# eBox_relay.net
KiCad netlist of a schematic drawn in Altium Designer
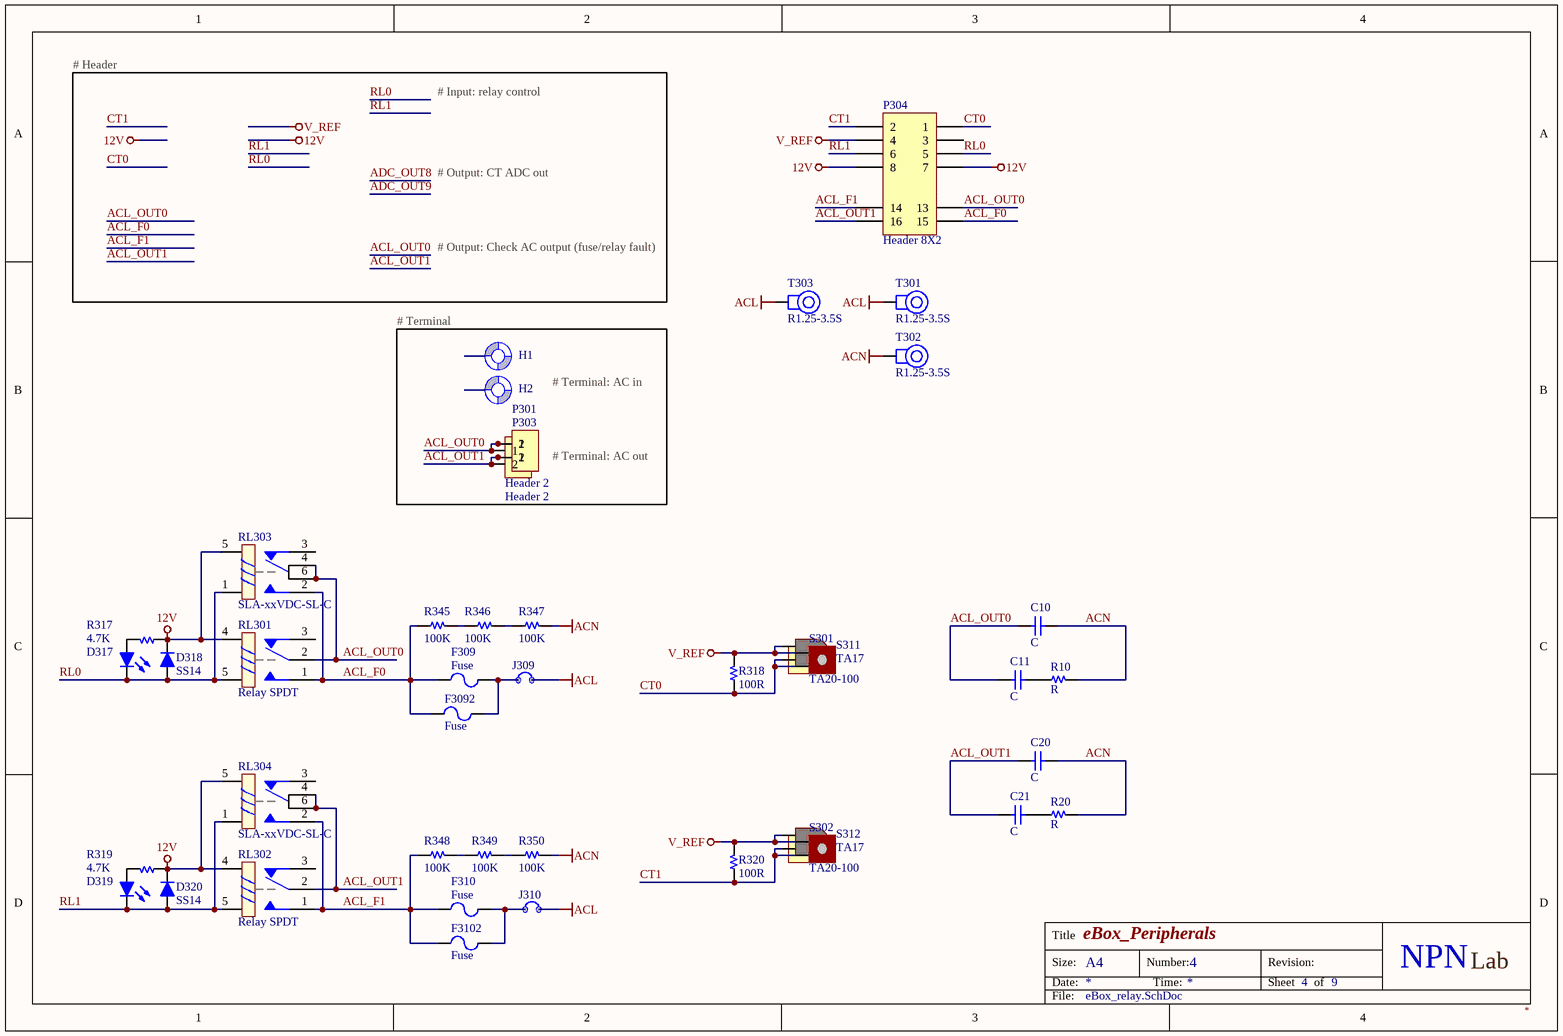
[diagram p0: eBox_relay.SchDoc]

(export (version "E")
  (design (tool "Eeschema 10.0.6"))
  (components
    (comp (ref "C10")
      (value "C")
      (footprint "CAP Ceramic/W300")
      (description "Capacitor non-pol")
      (libsource (lib "chipfc_altium_libs") (part "Capacitor NP"))
    )
    (comp (ref "C11")
      (value "C")
      (footprint "CAP Ceramic/W550")
      (description "Capacitor non-pol")
      (libsource (lib "chipfc_altium_libs") (part "Capacitor NP"))
    )
    (comp (ref "C20")
      (value "C")
      (footprint "CAP Ceramic/W300")
      (description "Capacitor non-pol")
      (libsource (lib "chipfc_altium_libs") (part "Capacitor NP"))
    )
    (comp (ref "C21")
      (value "C")
      (footprint "CAP Ceramic/W550")
      (description "Capacitor non-pol")
      (libsource (lib "chipfc_altium_libs") (part "Capacitor NP"))
    )
    (comp (ref "D317")
      (value "Led")
      (footprint "LED 3MM - green")
      (description "LED GREEN DIFFUSED 3MM ROUND T/H")
      (libsource (lib "chipfc_altium_libs") (part "Led"))
    )
    (comp (ref "D318")
      (value "SS14")
      (footprint "DO-214AC (SMA) L")
      (description "DIODE SCHOTTKY 40V 1A SMA")
      (libsource (lib "chipfc_altium_libs") (part "Diode"))
    )
    (comp (ref "D319")
      (value "Led")
      (footprint "LED 3MM - green")
      (description "LED GREEN DIFFUSED 3MM ROUND T/H")
      (libsource (lib "chipfc_altium_libs") (part "Led"))
    )
    (comp (ref "D320")
      (value "SS14")
      (footprint "DO-214AC (SMA) L")
      (description "DIODE SCHOTTKY 40V 1A SMA")
      (libsource (lib "chipfc_altium_libs") (part "Diode"))
    )
    (comp (ref "F309")
      (value "Fuse")
      (footprint "FUSE 2 DIP 0520 BOX")
      (libsource (lib "chipfc_altium_libs") (part "Fuse"))
    )
    (comp (ref "F310")
      (value "Fuse")
      (footprint "FUSE 2 DIP 0520 BOX")
      (libsource (lib "chipfc_altium_libs") (part "Fuse"))
    )
    (comp (ref "F3092")
      (value "Fuse")
      (footprint "FUSE 4 DIP 0630")
      (libsource (lib "chipfc_altium_libs") (part "Fuse"))
    )
    (comp (ref "F3102")
      (value "Fuse")
      (footprint "FUSE 4 DIP 0630")
      (libsource (lib "chipfc_altium_libs") (part "Fuse"))
    )
    (comp (ref "H1")
      (value "Screw Hole")
      (footprint "SCREW/3.2/7.0/M")
      (libsource (lib "chipfc_altium_libs") (part "Screw Hole"))
    )
    (comp (ref "H2")
      (value "Screw Hole")
      (footprint "SCREW/3.2/7.0/M")
      (libsource (lib "chipfc_altium_libs") (part "Screw Hole"))
    )
    (comp (ref "J309")
      (value "JUMP 2 CUSTOM")
      (footprint "JUMP/2/Custom")
      (libsource (lib "chipfc_altium_libs") (part "JUMP 2 CUSTOM"))
    )
    (comp (ref "J310")
      (value "JUMP 2 CUSTOM")
      (footprint "JUMP/2/Custom")
      (libsource (lib "chipfc_altium_libs") (part "JUMP 2 CUSTOM"))
    )
    (comp (ref "P301")
      (value "Header 2")
      (footprint "HDR/Terminal/2/KF1000")
      (description "Header, 2-Pin")
      (libsource (lib "chipfc_altium_libs") (part "Header 2"))
    )
    (comp (ref "P303")
      (value "Header 2")
      (footprint "HDR/Terminal/2/KF55C-10")
      (description "Header, 2-Pin")
      (libsource (lib "chipfc_altium_libs") (part "Header 2"))
    )
    (comp (ref "P304")
      (value "Header 8X2")
      (footprint "HDR/Header/16/DL/EDGE")
      (description "Header, 8-Pin, Dual row")
      (libsource (lib "chipfc_altium_libs") (part "Header 8X2"))
    )
    (comp (ref "P305")
      (value "Header 2")
      (footprint "HDR/Terminal/2/KF1000")
      (description "Header, 2-Pin")
      (libsource (lib "") (part "Header 2_1"))
    )
    (comp (ref "R10")
      (value "R")
      (footprint "R 1W")
      (description "Resistor")
      (libsource (lib "chipfc_altium_libs") (part "Resistor"))
    )
    (comp (ref "R20")
      (value "R")
      (footprint "R 1W")
      (description "Resistor")
      (libsource (lib "chipfc_altium_libs") (part "Resistor"))
    )
    (comp (ref "R317")
      (value "4.7K")
      (footprint "R 0603")
      (description "RES SMD 4.7K OHM 1% 1/10W 0805")
      (libsource (lib "chipfc_altium_libs") (part "Resistor"))
    )
    (comp (ref "R318")
      (value "100R")
      (footprint "R 0805")
      (description "RES SMD 100 OHM 1% 1/10W 0805")
      (libsource (lib "chipfc_altium_libs") (part "Resistor"))
    )
    (comp (ref "R319")
      (value "4.7K")
      (footprint "R 0603")
      (description "RES SMD 4.7K OHM 1% 1/10W 0805")
      (libsource (lib "chipfc_altium_libs") (part "Resistor"))
    )
    (comp (ref "R320")
      (value "100R")
      (footprint "R 0805")
      (description "RES SMD 100 OHM 1% 1/10W 0805")
      (libsource (lib "chipfc_altium_libs") (part "Resistor"))
    )
    (comp (ref "R345")
      (value "100K")
      (footprint "R 1206")
      (description "RES SMD 10K OHM 5% 1/4W 1206")
      (libsource (lib "chipfc_altium_libs") (part "Resistor"))
    )
    (comp (ref "R346")
      (value "100K")
      (footprint "R 1206")
      (description "RES SMD 10K OHM 5% 1/4W 1206")
      (libsource (lib "chipfc_altium_libs") (part "Resistor"))
    )
    (comp (ref "R347")
      (value "100K")
      (footprint "R 1206")
      (description "RES SMD 10K OHM 5% 1/4W 1206")
      (libsource (lib "chipfc_altium_libs") (part "Resistor"))
    )
    (comp (ref "R348")
      (value "100K")
      (footprint "R 1206")
      (description "RES SMD 10K OHM 5% 1/4W 1206")
      (libsource (lib "chipfc_altium_libs") (part "Resistor"))
    )
    (comp (ref "R349")
      (value "100K")
      (footprint "R 1206")
      (description "RES SMD 10K OHM 5% 1/4W 1206")
      (libsource (lib "chipfc_altium_libs") (part "Resistor"))
    )
    (comp (ref "R350")
      (value "100K")
      (footprint "R 1206")
      (description "RES SMD 10K OHM 5% 1/4W 1206")
      (libsource (lib "chipfc_altium_libs") (part "Resistor"))
    )
    (comp (ref "RL301")
      (value "Relay SPDT")
      (footprint "RL_SPDT_MIX")
      (libsource (lib "chipfc_altium_libs") (part "Relay SPDT"))
    )
    (comp (ref "RL302")
      (value "Relay SPDT")
      (footprint "RL_SPDT_MIX")
      (libsource (lib "chipfc_altium_libs") (part "Relay SPDT"))
    )
    (comp (ref "RL303")
      (value "SLA-xxVDC-SL-C")
      (footprint "RL_SPDT_30A")
      (libsource (lib "chipfc_altium_libs") (part "Relay SPDT_SLA"))
    )
    (comp (ref "RL304")
      (value "SLA-xxVDC-SL-C")
      (footprint "RL_SPDT_30A")
      (libsource (lib "chipfc_altium_libs") (part "Relay SPDT_SLA"))
    )
    (comp (ref "S301")
      (value "TA20-100")
      (footprint "TA20-100")
      (libsource (lib "chipfc_altium_libs") (part "TA20-100"))
    )
    (comp (ref "S302")
      (value "TA20-100")
      (footprint "TA20-100")
      (libsource (lib "chipfc_altium_libs") (part "TA20-100"))
    )
    (comp (ref "S309")
      (value "TA12-200")
      (footprint "TA12")
      (description "CURR SENSE 1:2000 5A T/H")
      (libsource (lib "chipfc_altium_libs") (part "TA12"))
    )
    (comp (ref "S310")
      (value "NA")
      (footprint "TA12")
      (description "CURR SENSE 1:2000 5A T/H")
      (fields (field (name "PART NO") "TA12-200"))
      (libsource (lib "chipfc_altium_libs") (part "TA12"))
    )
    (comp (ref "S311") (value "TA17") (footprint "TA17") (libsource (lib "chipfc_altium_libs") (part "TA17")))
    (comp (ref "S312") (value "TA17") (footprint "TA17") (libsource (lib "chipfc_altium_libs") (part "TA17")))
    (comp (ref "T301")
      (value "R1.25-3.5S")
      (footprint "R1.25-3.5S")
      (libsource (lib "chipfc_altium_libs") (part "R1.25-3.5S"))
    )
    (comp (ref "T302")
      (value "R1.25-3.5S")
      (footprint "R1.25-3.5S")
      (libsource (lib "chipfc_altium_libs") (part "R1.25-3.5S"))
    )
    (comp (ref "T303")
      (value "R1.25-3.5S")
      (footprint "R1.25-3.5S")
      (libsource (lib "chipfc_altium_libs") (part "R1.25-3.5S"))
    )
  )
  (nets
    (net (code "1") (name "/ACL_F0") (class "Default")
      (node (ref "F309") (pin "1") (pinfunction "1_1") (pintype "passive"))
      (node (ref "F3092") (pin "1") (pinfunction "1_1") (pintype "passive"))
      (node (ref "P304") (pin "15") (pinfunction "15_15") (pintype "passive"))
      (node (ref "R345") (pin "1") (pinfunction "1_1") (pintype "passive"))
      (node (ref "RL301") (pin "1") (pinfunction "COM_1") (pintype "passive"))
      (node (ref "RL303") (pin "2") (pinfunction "NO_2") (pintype "passive"))
    )
    (net (code "2") (name "/ACL_F1") (class "Default")
      (node (ref "F310") (pin "1") (pinfunction "1_1") (pintype "passive"))
      (node (ref "F3102") (pin "1") (pinfunction "1_1") (pintype "passive"))
      (node (ref "P304") (pin "14") (pinfunction "14_14") (pintype "passive"))
      (node (ref "R348") (pin "1") (pinfunction "1_1") (pintype "passive"))
      (node (ref "RL302") (pin "1") (pinfunction "COM_1") (pintype "passive"))
      (node (ref "RL304") (pin "2") (pinfunction "NO_2") (pintype "passive"))
    )
    (net (code "3") (name "/ACL_OUT0") (class "Default")
      (node (ref "C10") (pin "1") (pinfunction "1_1") (pintype "passive"))
      (node (ref "C11") (pin "1") (pinfunction "1_1") (pintype "passive"))
      (node (ref "P301") (pin "1") (pinfunction "1_1") (pintype "passive"))
      (node (ref "P303") (pin "1") (pinfunction "1_1") (pintype "passive"))
      (node (ref "P304") (pin "13") (pinfunction "13_13") (pintype "passive"))
      (node (ref "P305") (pin "2") (pinfunction "2_2") (pintype "passive"))
      (node (ref "RL301") (pin "2") (pinfunction "NO_2") (pintype "passive"))
      (node (ref "RL303") (pin "4") (pinfunction "COM_4") (pintype "passive"))
      (node (ref "RL303") (pin "6") (pinfunction "COM_6") (pintype "passive"))
    )
    (net (code "4") (name "/ACL_OUT1") (class "Default")
      (node (ref "C20") (pin "1") (pinfunction "1_1") (pintype "passive"))
      (node (ref "C21") (pin "1") (pinfunction "1_1") (pintype "passive"))
      (node (ref "P301") (pin "2") (pinfunction "2_2") (pintype "passive"))
      (node (ref "P303") (pin "2") (pinfunction "2_2") (pintype "passive"))
      (node (ref "P304") (pin "16") (pinfunction "16_16") (pintype "passive"))
      (node (ref "P305") (pin "1") (pinfunction "1_1") (pintype "passive"))
      (node (ref "RL302") (pin "2") (pinfunction "NO_2") (pintype "passive"))
      (node (ref "RL304") (pin "4") (pinfunction "COM_4") (pintype "passive"))
      (node (ref "RL304") (pin "6") (pinfunction "COM_6") (pintype "passive"))
    )
    (net (code "7") (name "/CT0") (class "Default")
      (node (ref "P304") (pin "1") (pinfunction "1_1") (pintype "passive"))
      (node (ref "R318") (pin "1") (pinfunction "1_1") (pintype "passive"))
      (node (ref "S301") (pin "4") (pinfunction "4_4") (pintype "passive"))
      (node (ref "S309") (pin "2") (pinfunction "2_2") (pintype "passive"))
      (node (ref "S311") (pin "2") (pinfunction "2_2") (pintype "passive"))
    )
    (net (code "8") (name "/CT1") (class "Default")
      (node (ref "P304") (pin "2") (pinfunction "2_2") (pintype "passive"))
      (node (ref "R320") (pin "1") (pinfunction "1_1") (pintype "passive"))
      (node (ref "S302") (pin "4") (pinfunction "4_4") (pintype "passive"))
      (node (ref "S310") (pin "2") (pinfunction "2_2") (pintype "passive"))
      (node (ref "S312") (pin "2") (pinfunction "2_2") (pintype "passive"))
    )
    (net (code "9") (name "/RL0") (class "Default")
      (node (ref "D317") (pin "2") (pinfunction "K_2") (pintype "passive"))
      (node (ref "D318") (pin "1") (pinfunction "A_1") (pintype "passive"))
      (node (ref "P304") (pin "5") (pinfunction "5_5") (pintype "passive"))
      (node (ref "RL301") (pin "5") (pinfunction "COIL2_5") (pintype "passive"))
      (node (ref "RL303") (pin "1") (pinfunction "COIL1_1") (pintype "passive"))
    )
    (net (code "10") (name "/RL1") (class "Default")
      (node (ref "D319") (pin "2") (pinfunction "K_2") (pintype "passive"))
      (node (ref "D320") (pin "1") (pinfunction "A_1") (pintype "passive"))
      (node (ref "P304") (pin "6") (pinfunction "6_6") (pintype "passive"))
      (node (ref "RL302") (pin "5") (pinfunction "COIL2_5") (pintype "passive"))
      (node (ref "RL304") (pin "1") (pinfunction "COIL1_1") (pintype "passive"))
    )
    (net (code "11") (name "12V") (class "Default")
      (node (ref "D318") (pin "2") (pinfunction "K_2") (pintype "passive"))
      (node (ref "D320") (pin "2") (pinfunction "K_2") (pintype "passive"))
      (node (ref "P304") (pin "7") (pinfunction "7_7") (pintype "passive"))
      (node (ref "P304") (pin "8") (pinfunction "8_8") (pintype "passive"))
      (node (ref "R317") (pin "1") (pinfunction "1_1") (pintype "passive"))
      (node (ref "R319") (pin "1") (pinfunction "1_1") (pintype "passive"))
      (node (ref "RL301") (pin "4") (pinfunction "COIL1_4") (pintype "passive"))
      (node (ref "RL302") (pin "4") (pinfunction "COIL1_4") (pintype "passive"))
      (node (ref "RL303") (pin "5") (pinfunction "COIL2_5") (pintype "passive"))
      (node (ref "RL304") (pin "5") (pinfunction "COIL2_5") (pintype "passive"))
    )
    (net (code "12") (name "ACL") (class "Default")
      (node (ref "J309") (pin "2") (pinfunction "2_2") (pintype "passive"))
      (node (ref "J310") (pin "2") (pinfunction "2_2") (pintype "passive"))
      (node (ref "T301") (pin "1") (pinfunction "1_1") (pintype "passive"))
      (node (ref "T303") (pin "1") (pinfunction "1_1") (pintype "passive"))
    )
    (net (code "13") (name "ACN") (class "Default")
      (node (ref "C10") (pin "2") (pinfunction "2_2") (pintype "passive"))
      (node (ref "C20") (pin "2") (pinfunction "2_2") (pintype "passive"))
      (node (ref "R10") (pin "2") (pinfunction "2_2") (pintype "passive"))
      (node (ref "R20") (pin "2") (pinfunction "2_2") (pintype "passive"))
      (node (ref "R347") (pin "2") (pinfunction "2_2") (pintype "passive"))
      (node (ref "R350") (pin "2") (pinfunction "2_2") (pintype "passive"))
      (node (ref "T302") (pin "1") (pinfunction "1_1") (pintype "passive"))
    )
    (net (code "14") (name "Net-(C11-Pad2)") (class "Default")
      (node (ref "C11") (pin "2") (pinfunction "2_2") (pintype "passive"))
      (node (ref "R10") (pin "1") (pinfunction "1_1") (pintype "passive"))
    )
    (net (code "15") (name "Net-(C21-Pad2)") (class "Default")
      (node (ref "C21") (pin "2") (pinfunction "2_2") (pintype "passive"))
      (node (ref "R20") (pin "1") (pinfunction "1_1") (pintype "passive"))
    )
    (net (code "16") (name "Net-(D317-A)") (class "Default")
      (node (ref "D317") (pin "1") (pinfunction "A_1") (pintype "passive"))
      (node (ref "R317") (pin "2") (pinfunction "2_2") (pintype "passive"))
    )
    (net (code "17") (name "Net-(D319-A)") (class "Default")
      (node (ref "D319") (pin "1") (pinfunction "A_1") (pintype "passive"))
      (node (ref "R319") (pin "2") (pinfunction "2_2") (pintype "passive"))
    )
    (net (code "18") (name "Net-(F309-Pad2)") (class "Default")
      (node (ref "F309") (pin "2") (pinfunction "2_2") (pintype "passive"))
      (node (ref "F3092") (pin "2") (pinfunction "2_2") (pintype "passive"))
      (node (ref "J309") (pin "1") (pinfunction "1_1") (pintype "passive"))
    )
    (net (code "19") (name "Net-(F310-Pad2)") (class "Default")
      (node (ref "F310") (pin "2") (pinfunction "2_2") (pintype "passive"))
      (node (ref "F3102") (pin "2") (pinfunction "2_2") (pintype "passive"))
      (node (ref "J310") (pin "1") (pinfunction "1_1") (pintype "passive"))
    )
    (net (code "20") (name "Net-(R345-Pad2)") (class "Default")
      (node (ref "R345") (pin "2") (pinfunction "2_2") (pintype "passive"))
      (node (ref "R346") (pin "1") (pinfunction "1_1") (pintype "passive"))
    )
    (net (code "21") (name "Net-(R346-Pad2)") (class "Default")
      (node (ref "R346") (pin "2") (pinfunction "2_2") (pintype "passive"))
      (node (ref "R347") (pin "1") (pinfunction "1_1") (pintype "passive"))
    )
    (net (code "22") (name "Net-(R348-Pad2)") (class "Default")
      (node (ref "R348") (pin "2") (pinfunction "2_2") (pintype "passive"))
      (node (ref "R349") (pin "1") (pinfunction "1_1") (pintype "passive"))
    )
    (net (code "23") (name "Net-(R349-Pad2)") (class "Default")
      (node (ref "R349") (pin "2") (pinfunction "2_2") (pintype "passive"))
      (node (ref "R350") (pin "1") (pinfunction "1_1") (pintype "passive"))
    )
    (net (code "24") (name "V_REF") (class "Default")
      (node (ref "P304") (pin "4") (pinfunction "4_4") (pintype "passive"))
      (node (ref "R318") (pin "2") (pinfunction "2_2") (pintype "passive"))
      (node (ref "R320") (pin "2") (pinfunction "2_2") (pintype "passive"))
      (node (ref "S301") (pin "3") (pinfunction "3_3") (pintype "passive"))
      (node (ref "S302") (pin "3") (pinfunction "3_3") (pintype "passive"))
      (node (ref "S309") (pin "1") (pinfunction "1_1") (pintype "passive"))
      (node (ref "S310") (pin "1") (pinfunction "1_1") (pintype "passive"))
      (node (ref "S311") (pin "1") (pinfunction "1_1") (pintype "passive"))
      (node (ref "S312") (pin "1") (pinfunction "1_1") (pintype "passive"))
    )
    (net (code "25") (name "unconnected-(H1-Screw-Pad1)") (class "Default")
      (node (ref "H1") (pin "1") (pinfunction "Screw_1") (pintype "passive"))
    )
    (net (code "26") (name "unconnected-(H2-Screw-Pad1)") (class "Default")
      (node (ref "H2") (pin "1") (pinfunction "Screw_1") (pintype "passive"))
    )
    (net (code "27") (name "unconnected-(P304-Pad3)") (class "Default")
      (node (ref "P304") (pin "3") (pinfunction "3_3") (pintype "passive"))
    )
    (net (code "28") (name "unconnected-(P304-Pad9)") (class "Default")
      (node (ref "P304") (pin "9") (pinfunction "9_9") (pintype "passive"))
    )
    (net (code "29") (name "unconnected-(P304-Pad10)") (class "Default")
      (node (ref "P304") (pin "10") (pinfunction "10_10") (pintype "passive"))
    )
    (net (code "30") (name "unconnected-(P304-Pad11)") (class "Default")
      (node (ref "P304") (pin "11") (pinfunction "11_11") (pintype "passive"))
    )
    (net (code "31") (name "unconnected-(P304-Pad12)") (class "Default")
      (node (ref "P304") (pin "12") (pinfunction "12_12") (pintype "passive"))
    )
    (net (code "32") (name "unconnected-(RL301-NC-Pad3)") (class "Default")
      (node (ref "RL301") (pin "3") (pinfunction "NC_3") (pintype "passive"))
    )
    (net (code "33") (name "unconnected-(RL302-NC-Pad3)") (class "Default")
      (node (ref "RL302") (pin "3") (pinfunction "NC_3") (pintype "passive"))
    )
    (net (code "34") (name "unconnected-(RL303-NC-Pad3)") (class "Default")
      (node (ref "RL303") (pin "3") (pinfunction "NC_3") (pintype "passive"))
    )
    (net (code "35") (name "unconnected-(RL304-NC-Pad3)") (class "Default")
      (node (ref "RL304") (pin "3") (pinfunction "NC_3") (pintype "passive"))
    )
  )
)
